# Gate_Driver_1.net
KiCad netlist of a schematic drawn in Altium Designer
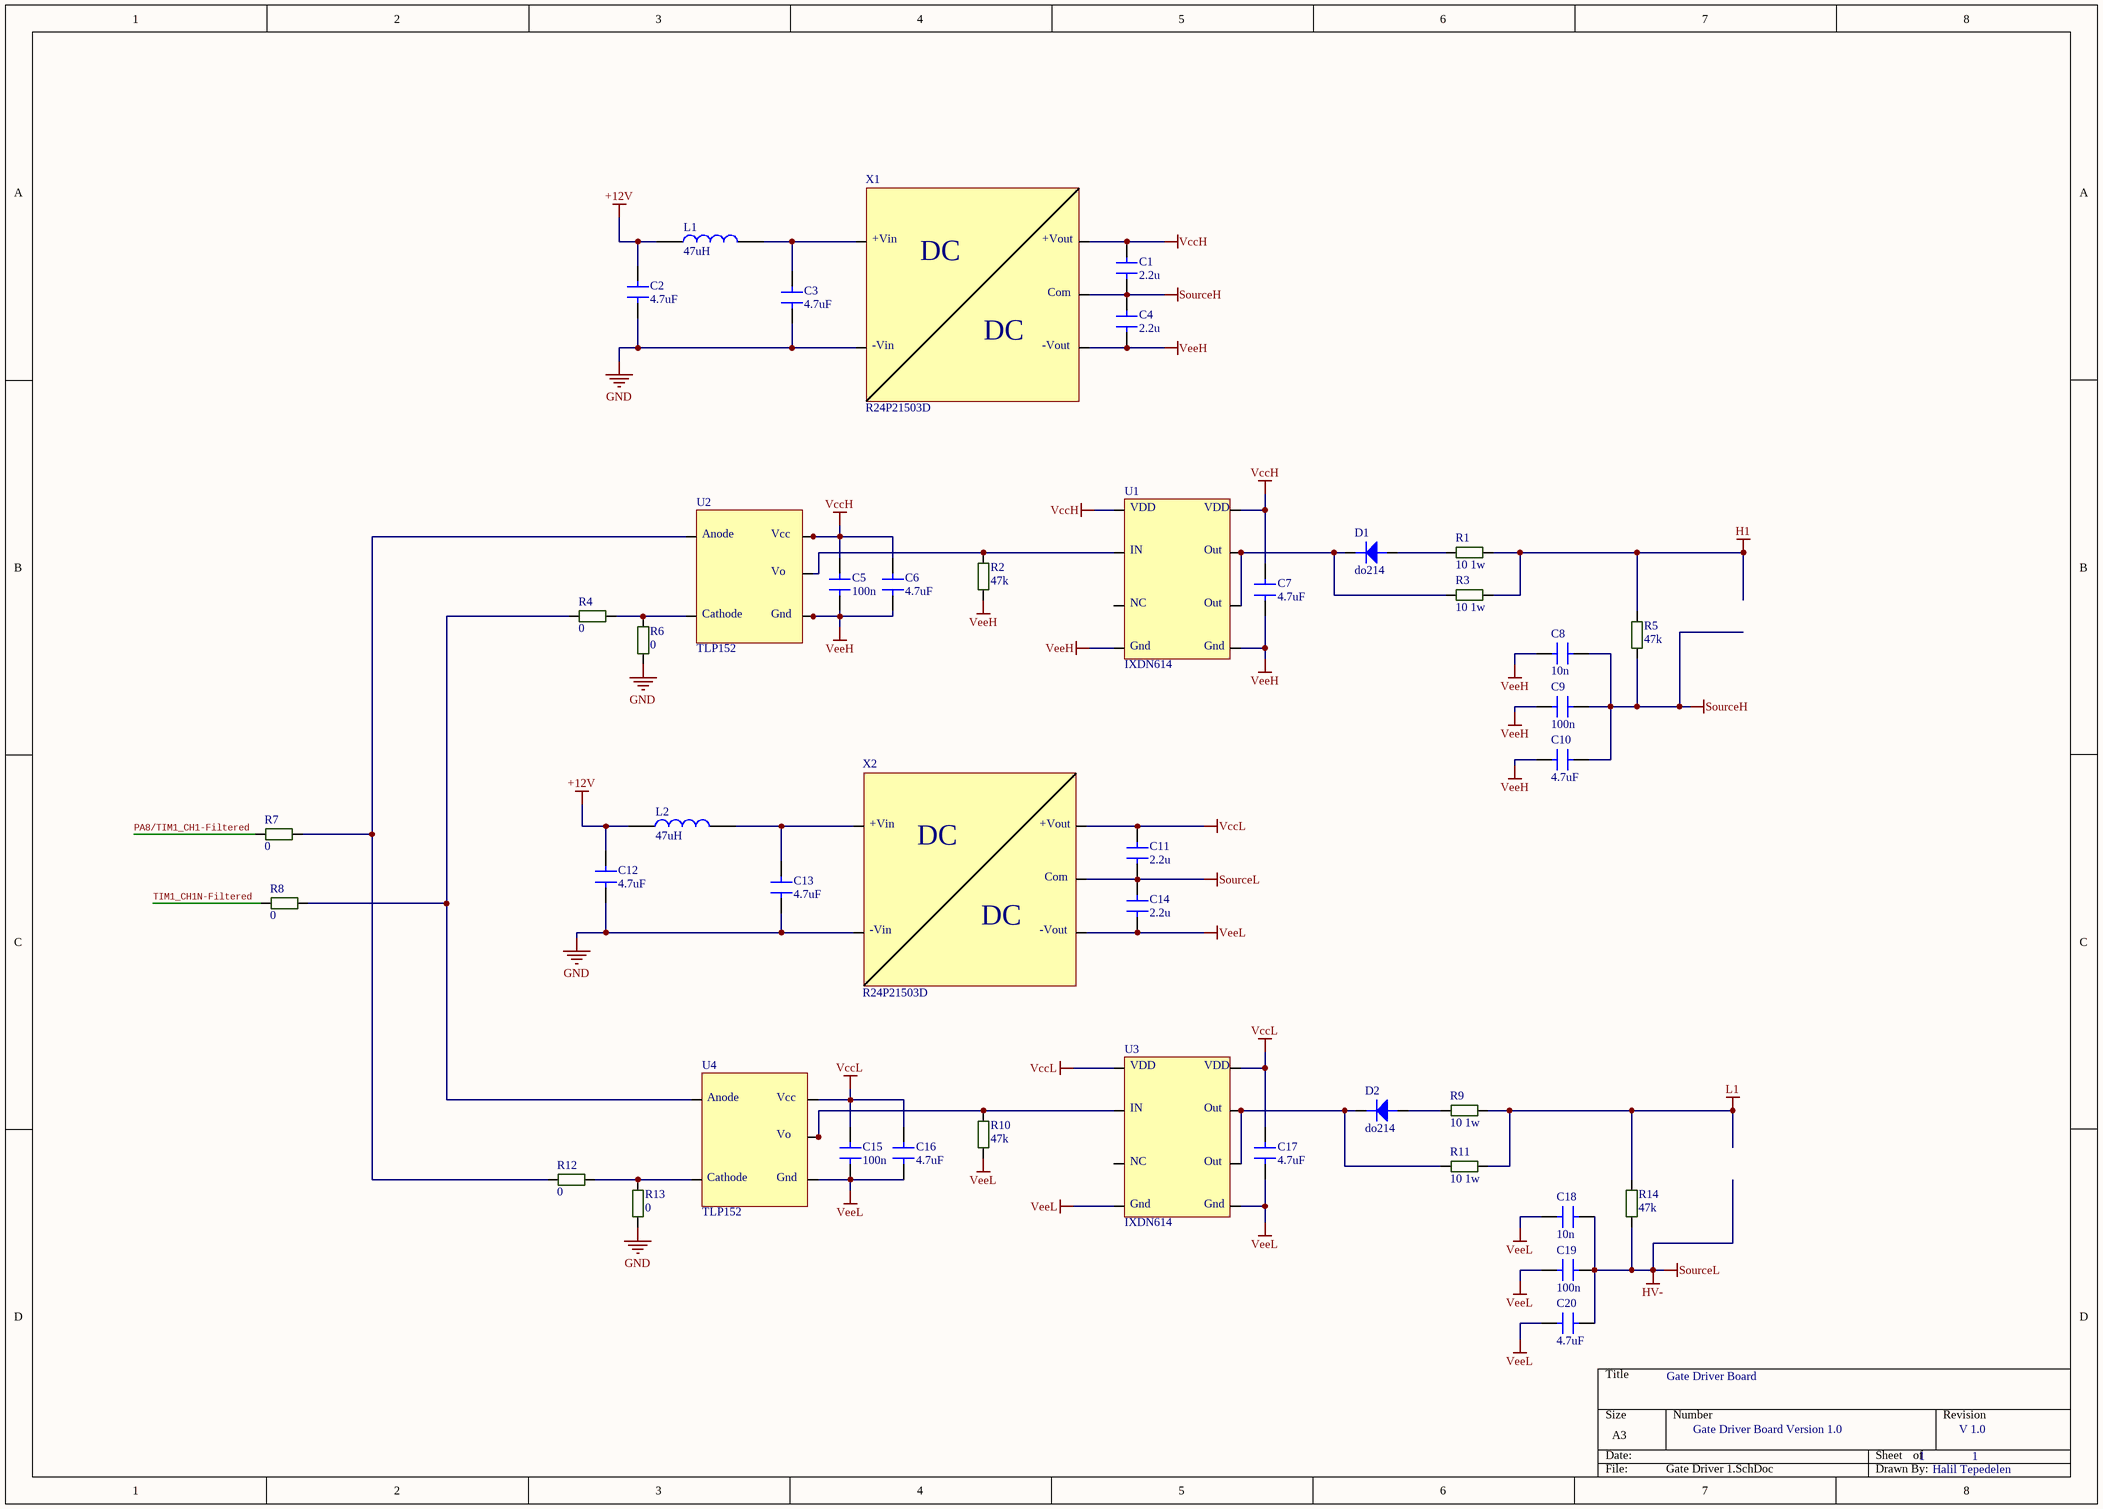
[diagram p0: Gate Driver 1.SchDoc]

(export (version "E")
  (design (tool "Eeschema 10.0.6"))
  (components
    (comp (ref "C1")
      (value "2.2u")
      (footprint "C-0805")
      (libsource (lib "Gate Driver Board") (part "C-0805"))
    )
    (comp (ref "C2")
      (value "4.7uF")
      (footprint "C-1206")
      (description "Cap1206 4.7uF")
      (fields (field (name "ÖZDISAN PART NUMBER") "CL31B475KBHNNNE") (field (name "MANUFACTURER") "SAMSUNG"))
      (libsource (lib "Gate Driver Board") (part "Cap1206"))
    )
    (comp (ref "C3")
      (value "4.7uF")
      (footprint "C-1206")
      (description "Cap1206 4.7uF")
      (fields (field (name "ÖZDISAN PART NUMBER") "CL31B475KBHNNNE") (field (name "MANUFACTURER") "SAMSUNG"))
      (libsource (lib "Gate Driver Board") (part "Cap1206"))
    )
    (comp (ref "C4")
      (value "2.2u")
      (footprint "C-0805")
      (libsource (lib "Gate Driver Board") (part "C-0805"))
    )
    (comp (ref "C5")
      (value "100n")
      (footprint "C-0805")
      (libsource (lib "Gate Driver Board") (part "C-0805"))
    )
    (comp (ref "C6")
      (value "4.7uF")
      (footprint "C-1206")
      (description "Cap1206 4.7uF")
      (libsource (lib "Gate Driver Board") (part "C-1206"))
    )
    (comp (ref "C7")
      (value "4.7uF")
      (footprint "C-1206")
      (description "Cap1206 4.7uF")
      (libsource (lib "Gate Driver Board") (part "C-1206"))
    )
    (comp (ref "C8") (value "10n") (footprint "C-0805") (libsource (lib "Gate Driver Board") (part "C-0805")))
    (comp (ref "C9")
      (value "100n")
      (footprint "C-0805")
      (libsource (lib "Gate Driver Board") (part "C-0805"))
    )
    (comp (ref "C10")
      (value "4.7uF")
      (footprint "C-1206")
      (description "Cap1206 4.7uF")
      (fields (field (name "ÖZDISAN PART NUMBER") " CL31B475KBHNNNE") (field (name "MANUFACTURER") "SAMSUNG"))
      (libsource (lib "Gate Driver Board") (part "Cap1206"))
    )
    (comp (ref "C11")
      (value "2.2u")
      (footprint "C-0805")
      (libsource (lib "Gate Driver Board") (part "C-0805"))
    )
    (comp (ref "C12")
      (value "4.7uF")
      (footprint "C-1206")
      (description "Cap1206 4.7uF")
      (fields (field (name "ÖZDISAN PART NUMBER") "CL31B475KBHNNNE") (field (name "MANUFACTURER") "SAMSUNG"))
      (libsource (lib "Gate Driver Board") (part "Cap1206"))
    )
    (comp (ref "C13")
      (value "4.7uF")
      (footprint "C-1206")
      (description "Cap1206 4.7uF")
      (fields (field (name "ÖZDISAN PART NUMBER") " CL31B475KBHNNNE") (field (name "MANUFACTURER") "SAMSUNG"))
      (libsource (lib "Gate Driver Board") (part "Cap1206"))
    )
    (comp (ref "C14")
      (value "2.2u")
      (footprint "C-0805")
      (libsource (lib "Gate Driver Board") (part "C-0805"))
    )
    (comp (ref "C15")
      (value "100n")
      (footprint "C-0805")
      (libsource (lib "Gate Driver Board") (part "C-0805"))
    )
    (comp (ref "C16")
      (value "4.7uF")
      (footprint "C-1206")
      (description "Cap1206 4.7uF")
      (libsource (lib "Gate Driver Board") (part "C-1206"))
    )
    (comp (ref "C17")
      (value "4.7uF")
      (footprint "C-1206")
      (description "Cap1206 4.7uF")
      (libsource (lib "Gate Driver Board") (part "C-1206"))
    )
    (comp (ref "C18")
      (value "10n")
      (footprint "C-0805")
      (libsource (lib "Gate Driver Board") (part "C-0805"))
    )
    (comp (ref "C19")
      (value "100n")
      (footprint "C-0805")
      (libsource (lib "Gate Driver Board") (part "C-0805"))
    )
    (comp (ref "C20")
      (value "4.7uF")
      (footprint "C-1206")
      (description "Cap1206 4.7uF")
      (fields (field (name "ÖZDISAN PART NUMBER") "CL31B475KBHNNNE") (field (name "MANUFACTURER") "SAMSUNG"))
      (libsource (lib "Gate Driver Board") (part "Cap1206"))
    )
    (comp (ref "D1")
      (value "do214")
      (footprint "DO-214AC")
      (description "DIODE FAST SWITCHING Single 150mA 75V SMT SOD323")
      (libsource (lib "Gate Driver Board") (part "do214"))
    )
    (comp (ref "D2")
      (value "do214")
      (footprint "DO-214AC")
      (description "DIODE FAST SWITCHING Single 150mA 75V SMT SOD323")
      (libsource (lib "Gate Driver Board") (part "do214"))
    )
    (comp (ref "L1")
      (value "47uH")
      (footprint "WE-TPC_282892")
      (libsource (lib "Gate Driver Board") (part "inductor"))
    )
    (comp (ref "L2")
      (value "47uH")
      (footprint "WE-TPC_282892")
      (libsource (lib "Gate Driver Board") (part "inductor"))
    )
    (comp (ref "R1")
      (value "10 1w")
      (footprint "R-2512")
      (description "R-2512 10R 1W")
      (libsource (lib "Gate Driver Board") (part "R-2512"))
    )
    (comp (ref "R2")
      (value "47k")
      (footprint "R-0805")
      (description "Res0805 47K R")
      (fields (field (name "MANUFACTURER") "ROYALOHM") (field (name "ÖZDISAN PART NUMBER") "0805S8J0473T5E"))
      (libsource (lib "Gate Driver Board") (part "Res0805"))
    )
    (comp (ref "R3")
      (value "10 1w")
      (footprint "R-2512")
      (description "R-2512 10R 1W")
      (libsource (lib "Gate Driver Board") (part "R-2512"))
    )
    (comp (ref "R4")
      (value "0")
      (footprint "R-0805")
      (description "Res0805 0R")
      (fields (field (name "MANUFACTURER") "ROYALOHM") (field (name "ÖZDISAN PART NUMBER") "0805S8J0000T5E"))
      (libsource (lib "Gate Driver Board") (part "Res0805"))
    )
    (comp (ref "R5")
      (value "47k")
      (footprint "R-0805")
      (description "Res0805 47K R")
      (fields (field (name "ÖZDISAN PART NUMBER") "0805S8J0473T5E") (field (name "MANUFACTURER") "ROYALOHM"))
      (libsource (lib "Gate Driver Board") (part "Res0805"))
    )
    (comp (ref "R6")
      (value "0")
      (footprint "R-0805")
      (description "Res0805 0R")
      (fields (field (name "MANUFACTURER") "ROYALOHM") (field (name "ÖZDISAN PART NUMBER") "0805S8J0000T5E"))
      (libsource (lib "Gate Driver Board") (part "Res0805"))
    )
    (comp (ref "R7")
      (value "0")
      (footprint "R-0805")
      (description "Res0805 0R")
      (fields (field (name "MANUFACTURER") "ROYALOHM") (field (name "ÖZDISAN PART NUMBER") "0805S8J0000T5E"))
      (libsource (lib "Gate Driver Board") (part "Res0805"))
    )
    (comp (ref "R8")
      (value "0")
      (footprint "R-0805")
      (description "Res0805 0R")
      (fields (field (name "MANUFACTURER") "ROYALOHM") (field (name "ÖZDISAN PART NUMBER") "0805S8J0000T5E"))
      (libsource (lib "Gate Driver Board") (part "Res0805"))
    )
    (comp (ref "R9")
      (value "10 1w")
      (footprint "R-2512")
      (description "R-2512 10R 1W")
      (libsource (lib "Gate Driver Board") (part "R-2512"))
    )
    (comp (ref "R10")
      (value "47k")
      (footprint "R-0805")
      (description "Res0805 47K R")
      (fields (field (name "ÖZDISAN PART NUMBER") "0805S8J0473T5E") (field (name "MANUFACTURER") "ROYALOHM"))
      (libsource (lib "Gate Driver Board") (part "Res0805"))
    )
    (comp (ref "R11")
      (value "10 1w")
      (footprint "R-2512")
      (description "R-2512 10R 1W")
      (libsource (lib "Gate Driver Board") (part "R-2512"))
    )
    (comp (ref "R12")
      (value "0")
      (footprint "R-0805")
      (description "Res0805 0R")
      (fields (field (name "MANUFACTURER") "ROYALOHM") (field (name "ÖZDISAN PART NUMBER") "0805S8J0000T5E"))
      (libsource (lib "Gate Driver Board") (part "Res0805"))
    )
    (comp (ref "R13")
      (value "0")
      (footprint "R-0805")
      (description "Res0805 0R")
      (fields (field (name "MANUFACTURER") "ROYALOHM") (field (name "ÖZDISAN PART NUMBER") "0805S8J0000T5E"))
      (libsource (lib "Gate Driver Board") (part "Res0805"))
    )
    (comp (ref "R14")
      (value "47k")
      (footprint "R-0805")
      (description "Res0805 47K R")
      (fields (field (name "ÖZDISAN PART NUMBER") "0805S8J0473T5E") (field (name "MANUFACTURER") "ROYALOHM"))
      (libsource (lib "Gate Driver Board") (part "Res0805"))
    )
    (comp (ref "U1")
      (value "IXDN614")
      (footprint "FAN3122 Soic8")
      (description "14A 8SOIC EXP MTL NON INVERTING")
      (fields
        (field (name "MANUFACTURER") "Ixys Clare")
        (field (name "MANUFACTURER PART NUMBER") "IXDN614SITR")
      )
      (libsource (lib "Gate Driver Board") (part "IXDN614SITR"))
    )
    (comp (ref "U2")
      (value "TLP152")
      (footprint "TLP152")
      (description "OPTOISO 3.75KV GATE DRIVER 6SO-5")
      (fields
        (field (name "MANUFACTURER") "Toshiba")
        (field (name "MANUFACTURER PART NUMBER") "TLP152(TPL,E")
      )
      (libsource (lib "Gate Driver Board") (part "TLP152(TPL,E"))
    )
    (comp (ref "U3")
      (value "IXDN614")
      (footprint "FAN3122 Soic8")
      (description "14A 8SOIC EXP MTL NON INVERTING")
      (fields
        (field (name "MANUFACTURER") "Ixys Clare")
        (field (name "MANUFACTURER PART NUMBER") "IXDN614SITR")
      )
      (libsource (lib "Gate Driver Board") (part "IXDN614SITR"))
    )
    (comp (ref "U4")
      (value "TLP152")
      (footprint "TLP152")
      (description "OPTOISO 3.75KV GATE DRIVER 6SO-5")
      (fields
        (field (name "MANUFACTURER") "Toshiba")
        (field (name "MANUFACTURER PART NUMBER") "TLP152(TPL,E")
      )
      (libsource (lib "Gate Driver Board") (part "TLP152(TPL,E"))
    )
    (comp (ref "X1")
      (value "R24P21503D")
      (footprint "SIP7")
      (fields (field (name "MANUFACTURER") "Recom"))
      (libsource (lib "Gate Driver Board") (part "R24P21503D"))
    )
    (comp (ref "X2")
      (value "R24P21503D")
      (footprint "SIP7")
      (fields (field (name "MANUFACTURER") "Recom"))
      (libsource (lib "Gate Driver Board") (part "R24P21503D"))
    )
  )
  (nets
    (net (code "1") (name "+12V") (class "Default")
      (node (ref "C12") (pin "2") (pinfunction "2_2") (pintype "passive"))
      (node (ref "C2") (pin "2") (pinfunction "2_2") (pintype "passive"))
      (node (ref "L1") (pin "1") (pinfunction "1_1") (pintype "passive"))
      (node (ref "L2") (pin "1") (pinfunction "1_1") (pintype "passive"))
    )
    (net (code "2") (name "/PA8{slash}TIM1_CH1-Filtered") (class "Default")
      (node (ref "R7") (pin "1") (pinfunction "1_1") (pintype "passive"))
    )
    (net (code "3") (name "/TIM1_CH1N-Filtered") (class "Default")
      (node (ref "R8") (pin "1") (pinfunction "1_1") (pintype "passive"))
    )
    (net (code "4") (name "GND") (class "Default")
      (node (ref "C12") (pin "1") (pinfunction "1_1") (pintype "passive"))
      (node (ref "C13") (pin "1") (pinfunction "1_1") (pintype "passive"))
      (node (ref "C2") (pin "1") (pinfunction "1_1") (pintype "passive"))
      (node (ref "C3") (pin "1") (pinfunction "1_1") (pintype "passive"))
      (node (ref "R13") (pin "1") (pinfunction "1_1") (pintype "passive"))
      (node (ref "R6") (pin "1") (pinfunction "1_1") (pintype "passive"))
      (node (ref "X1") (pin "2") (pinfunction "2_2") (pintype "passive"))
      (node (ref "X2") (pin "2") (pinfunction "2_2") (pintype "passive"))
    )
    (net (code "5") (name "H1") (class "Default")
      (node (ref "R1") (pin "2") (pinfunction "2_2") (pintype "passive"))
      (node (ref "R3") (pin "2") (pinfunction "2_2") (pintype "passive"))
      (node (ref "R5") (pin "2") (pinfunction "2_2") (pintype "passive"))
    )
    (net (code "6") (name "HV-") (class "Default")
      (node (ref "C11") (pin "1") (pinfunction "1_1") (pintype "passive"))
      (node (ref "C14") (pin "2") (pinfunction "2_2") (pintype "passive"))
      (node (ref "C18") (pin "1") (pinfunction "1_1") (pintype "passive"))
      (node (ref "C19") (pin "1") (pinfunction "1_1") (pintype "passive"))
      (node (ref "C20") (pin "2") (pinfunction "2_2") (pintype "passive"))
      (node (ref "R14") (pin "1") (pinfunction "1_1") (pintype "passive"))
      (node (ref "X2") (pin "6") (pinfunction "6_6") (pintype "passive"))
    )
    (net (code "7") (name "L1") (class "Default")
      (node (ref "R11") (pin "2") (pinfunction "2_2") (pintype "passive"))
      (node (ref "R14") (pin "2") (pinfunction "2_2") (pintype "passive"))
      (node (ref "R9") (pin "2") (pinfunction "2_2") (pintype "passive"))
    )
    (net (code "8") (name "Net-(C3-Pad2)") (class "Default")
      (node (ref "C3") (pin "2") (pinfunction "2_2") (pintype "passive"))
      (node (ref "L1") (pin "2") (pinfunction "2_2") (pintype "passive"))
      (node (ref "X1") (pin "1") (pinfunction "1_1") (pintype "passive"))
    )
    (net (code "9") (name "Net-(C13-Pad2)") (class "Default")
      (node (ref "C13") (pin "2") (pinfunction "2_2") (pintype "passive"))
      (node (ref "L2") (pin "2") (pinfunction "2_2") (pintype "passive"))
      (node (ref "X2") (pin "1") (pinfunction "1_1") (pintype "passive"))
    )
    (net (code "10") (name "Net-(D1-Pada)") (class "Default")
      (node (ref "D1") (pin "a") (pinfunction "a_a") (pintype "passive"))
      (node (ref "R1") (pin "1") (pinfunction "1_1") (pintype "passive"))
    )
    (net (code "11") (name "Net-(D1-Padk)") (class "Default")
      (node (ref "D1") (pin "k") (pinfunction "k_k") (pintype "passive"))
      (node (ref "R3") (pin "1") (pinfunction "1_1") (pintype "passive"))
      (node (ref "U1") (pin "6") (pinfunction "6_6") (pintype "passive"))
      (node (ref "U1") (pin "7") (pinfunction "7_7") (pintype "passive"))
    )
    (net (code "12") (name "Net-(D2-Pada)") (class "Default")
      (node (ref "D2") (pin "a") (pinfunction "a_a") (pintype "passive"))
      (node (ref "R9") (pin "1") (pinfunction "1_1") (pintype "passive"))
    )
    (net (code "13") (name "Net-(D2-Padk)") (class "Default")
      (node (ref "D2") (pin "k") (pinfunction "k_k") (pintype "passive"))
      (node (ref "R11") (pin "1") (pinfunction "1_1") (pintype "passive"))
      (node (ref "U3") (pin "6") (pinfunction "6_6") (pintype "passive"))
      (node (ref "U3") (pin "7") (pinfunction "7_7") (pintype "passive"))
    )
    (net (code "14") (name "Net-(R2-Pad2)") (class "Default")
      (node (ref "R2") (pin "2") (pinfunction "2_2") (pintype "passive"))
      (node (ref "U1") (pin "2") (pinfunction "2_2") (pintype "passive"))
      (node (ref "U2") (pin "4") (pinfunction "4_4") (pintype "passive"))
    )
    (net (code "15") (name "Net-(R4-Pad1)") (class "Default")
      (node (ref "R4") (pin "1") (pinfunction "1_1") (pintype "passive"))
      (node (ref "R8") (pin "2") (pinfunction "2_2") (pintype "passive"))
      (node (ref "U4") (pin "1") (pinfunction "1_1") (pintype "passive"))
    )
    (net (code "16") (name "Net-(R4-Pad2)") (class "Default")
      (node (ref "R4") (pin "2") (pinfunction "2_2") (pintype "passive"))
      (node (ref "R6") (pin "2") (pinfunction "2_2") (pintype "passive"))
      (node (ref "U2") (pin "2") (pinfunction "2_2") (pintype "passive"))
    )
    (net (code "17") (name "Net-(R10-Pad2)") (class "Default")
      (node (ref "R10") (pin "2") (pinfunction "2_2") (pintype "passive"))
      (node (ref "U3") (pin "2") (pinfunction "2_2") (pintype "passive"))
      (node (ref "U4") (pin "4") (pinfunction "4_4") (pintype "passive"))
    )
    (net (code "18") (name "Net-(R12-Pad1)") (class "Default")
      (node (ref "R12") (pin "1") (pinfunction "1_1") (pintype "passive"))
      (node (ref "R7") (pin "2") (pinfunction "2_2") (pintype "passive"))
      (node (ref "U2") (pin "1") (pinfunction "1_1") (pintype "passive"))
    )
    (net (code "19") (name "Net-(R12-Pad2)") (class "Default")
      (node (ref "R12") (pin "2") (pinfunction "2_2") (pintype "passive"))
      (node (ref "R13") (pin "2") (pinfunction "2_2") (pintype "passive"))
      (node (ref "U4") (pin "2") (pinfunction "2_2") (pintype "passive"))
    )
    (net (code "20") (name "SourceH") (class "Default")
      (node (ref "C1") (pin "1") (pinfunction "1_1") (pintype "passive"))
      (node (ref "C10") (pin "2") (pinfunction "2_2") (pintype "passive"))
      (node (ref "C4") (pin "2") (pinfunction "2_2") (pintype "passive"))
      (node (ref "C8") (pin "1") (pinfunction "1_1") (pintype "passive"))
      (node (ref "C9") (pin "1") (pinfunction "1_1") (pintype "passive"))
      (node (ref "R5") (pin "1") (pinfunction "1_1") (pintype "passive"))
      (node (ref "X1") (pin "6") (pinfunction "6_6") (pintype "passive"))
    )
    (net (code "21") (name "VccH") (class "Default")
      (node (ref "C1") (pin "2") (pinfunction "2_2") (pintype "passive"))
      (node (ref "C5") (pin "2") (pinfunction "2_2") (pintype "passive"))
      (node (ref "C6") (pin "2") (pinfunction "2_2") (pintype "passive"))
      (node (ref "C7") (pin "2") (pinfunction "2_2") (pintype "passive"))
      (node (ref "U1") (pin "1") (pinfunction "1_1") (pintype "passive"))
      (node (ref "U1") (pin "8") (pinfunction "8_8") (pintype "passive"))
      (node (ref "U2") (pin "5") (pinfunction "5_5") (pintype "passive"))
      (node (ref "X1") (pin "7") (pinfunction "7_7") (pintype "passive"))
    )
    (net (code "22") (name "VccL") (class "Default")
      (node (ref "C11") (pin "2") (pinfunction "2_2") (pintype "passive"))
      (node (ref "C15") (pin "2") (pinfunction "2_2") (pintype "passive"))
      (node (ref "C16") (pin "2") (pinfunction "2_2") (pintype "passive"))
      (node (ref "C17") (pin "2") (pinfunction "2_2") (pintype "passive"))
      (node (ref "U3") (pin "1") (pinfunction "1_1") (pintype "passive"))
      (node (ref "U3") (pin "8") (pinfunction "8_8") (pintype "passive"))
      (node (ref "U4") (pin "5") (pinfunction "5_5") (pintype "passive"))
      (node (ref "X2") (pin "7") (pinfunction "7_7") (pintype "passive"))
    )
    (net (code "23") (name "VeeH") (class "Default")
      (node (ref "C10") (pin "1") (pinfunction "1_1") (pintype "passive"))
      (node (ref "C4") (pin "1") (pinfunction "1_1") (pintype "passive"))
      (node (ref "C5") (pin "1") (pinfunction "1_1") (pintype "passive"))
      (node (ref "C6") (pin "1") (pinfunction "1_1") (pintype "passive"))
      (node (ref "C7") (pin "1") (pinfunction "1_1") (pintype "passive"))
      (node (ref "C8") (pin "2") (pinfunction "2_2") (pintype "passive"))
      (node (ref "C9") (pin "2") (pinfunction "2_2") (pintype "passive"))
      (node (ref "R2") (pin "1") (pinfunction "1_1") (pintype "passive"))
      (node (ref "U1") (pin "4") (pinfunction "4_4") (pintype "passive"))
      (node (ref "U1") (pin "5") (pinfunction "5_5") (pintype "passive"))
      (node (ref "U2") (pin "3") (pinfunction "3_3") (pintype "passive"))
      (node (ref "X1") (pin "5") (pinfunction "5_5") (pintype "passive"))
    )
    (net (code "24") (name "VeeL") (class "Default")
      (node (ref "C14") (pin "1") (pinfunction "1_1") (pintype "passive"))
      (node (ref "C15") (pin "1") (pinfunction "1_1") (pintype "passive"))
      (node (ref "C16") (pin "1") (pinfunction "1_1") (pintype "passive"))
      (node (ref "C17") (pin "1") (pinfunction "1_1") (pintype "passive"))
      (node (ref "C18") (pin "2") (pinfunction "2_2") (pintype "passive"))
      (node (ref "C19") (pin "2") (pinfunction "2_2") (pintype "passive"))
      (node (ref "C20") (pin "1") (pinfunction "1_1") (pintype "passive"))
      (node (ref "R10") (pin "1") (pinfunction "1_1") (pintype "passive"))
      (node (ref "U3") (pin "4") (pinfunction "4_4") (pintype "passive"))
      (node (ref "U3") (pin "5") (pinfunction "5_5") (pintype "passive"))
      (node (ref "U4") (pin "3") (pinfunction "3_3") (pintype "passive"))
      (node (ref "X2") (pin "5") (pinfunction "5_5") (pintype "passive"))
    )
    (net (code "25") (name "unconnected-(U1-Pad3)") (class "Default")
      (node (ref "U1") (pin "3") (pinfunction "3_3") (pintype "passive"))
    )
    (net (code "26") (name "unconnected-(U3-Pad3)") (class "Default")
      (node (ref "U3") (pin "3") (pinfunction "3_3") (pintype "passive"))
    )
  )
)
